# Power.net
KiCad netlist of a schematic drawn in Altium Designer
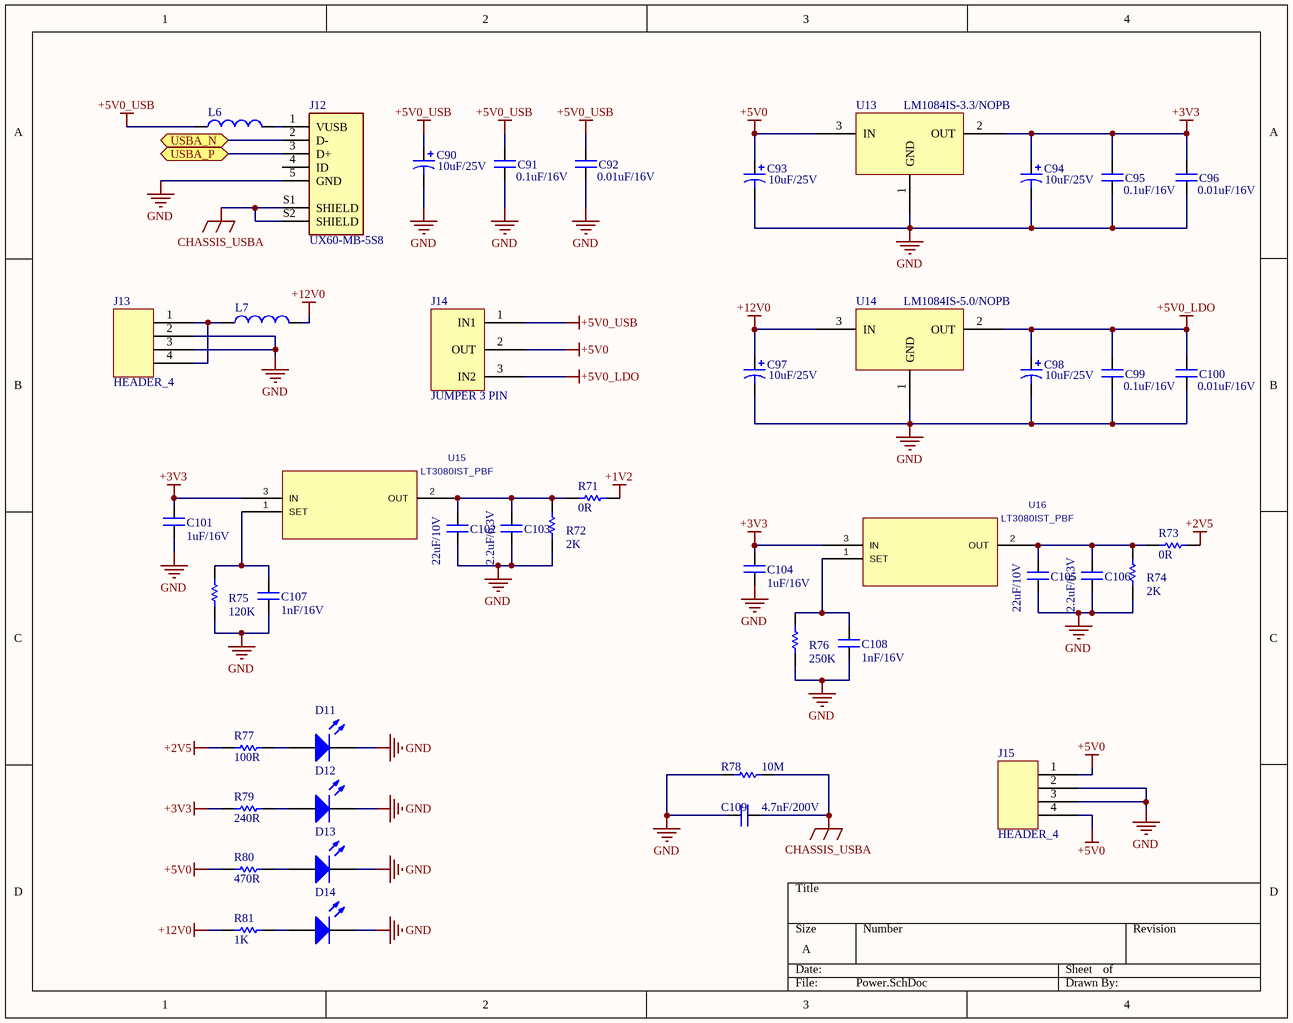
[diagram p0: Power.SchDoc]

(export (version "E")
  (design (tool "Eeschema 10.0.6"))
  (components
    (comp (ref "C90")
      (value "10uF/25V")
      (footprint "CASE-C")
      (fields (field (name "Comment") "CASE-C"))
      (libsource (lib "AdapterLib") (part "CASE-C"))
    )
    (comp (ref "C91")
      (value "0.1uF/16V")
      (footprint "CAP_0805")
      (fields (field (name "Comment") "CAP_0805"))
      (libsource (lib "AdapterLib") (part "CAP_0805"))
    )
    (comp (ref "C92")
      (value "0.01uF/16V")
      (footprint "CAP_0805")
      (fields (field (name "Comment") "CAP_0805"))
      (libsource (lib "AdapterLib") (part "CAP_0805"))
    )
    (comp (ref "C93")
      (value "10uF/25V")
      (footprint "CASE-C")
      (fields (field (name "Comment") "CASE-C"))
      (libsource (lib "AdapterLib") (part "CASE-C"))
    )
    (comp (ref "C94")
      (value "10uF/25V")
      (footprint "CASE-C")
      (fields (field (name "Comment") "CASE-C"))
      (libsource (lib "AdapterLib") (part "CASE-C"))
    )
    (comp (ref "C95")
      (value "0.1uF/16V")
      (footprint "CAP_0805")
      (fields (field (name "Comment") "CAP_0805"))
      (libsource (lib "AdapterLib") (part "CAP_0805"))
    )
    (comp (ref "C96")
      (value "0.01uF/16V")
      (footprint "CAP_0805")
      (fields (field (name "Comment") "CAP_0805"))
      (libsource (lib "AdapterLib") (part "CAP_0805"))
    )
    (comp (ref "C97")
      (value "10uF/25V")
      (footprint "CASE-C")
      (fields (field (name "Comment") "CASE-C"))
      (libsource (lib "AdapterLib") (part "CASE-C"))
    )
    (comp (ref "C98")
      (value "10uF/25V")
      (footprint "CASE-C")
      (fields (field (name "Comment") "CASE-C"))
      (libsource (lib "AdapterLib") (part "CASE-C"))
    )
    (comp (ref "C99")
      (value "0.1uF/16V")
      (footprint "CAP_0805")
      (fields (field (name "Comment") "CAP_0805"))
      (libsource (lib "AdapterLib") (part "CAP_0805"))
    )
    (comp (ref "C100")
      (value "0.01uF/16V")
      (footprint "CAP_0805")
      (fields (field (name "Comment") "CAP_0805"))
      (libsource (lib "AdapterLib") (part "CAP_0805"))
    )
    (comp (ref "C101")
      (value "1uF/16V")
      (footprint "CAP_0805")
      (fields (field (name "Comment") "CAP_0805"))
      (libsource (lib "AdapterLib") (part "CAP_0805"))
    )
    (comp (ref "C102")
      (value "22uF/10V")
      (footprint "CAP_0805")
      (fields (field (name "Comment") "CAP_0805"))
      (libsource (lib "AdapterLib") (part "CAP_0805"))
    )
    (comp (ref "C103")
      (value "2.2uF/6.3V")
      (footprint "CAP_0805")
      (fields (field (name "Comment") "CAP_0805"))
      (libsource (lib "AdapterLib") (part "CAP_0805"))
    )
    (comp (ref "C104")
      (value "1uF/16V")
      (footprint "CAP_0805")
      (fields (field (name "Comment") "CAP_0805"))
      (libsource (lib "AdapterLib") (part "CAP_0805"))
    )
    (comp (ref "C105")
      (value "22uF/10V")
      (footprint "CAP_0805")
      (fields (field (name "Comment") "CAP_0805"))
      (libsource (lib "AdapterLib") (part "CAP_0805"))
    )
    (comp (ref "C106")
      (value "2.2uF/6.3V")
      (footprint "CAP_0805")
      (fields (field (name "Comment") "CAP_0805"))
      (libsource (lib "AdapterLib") (part "CAP_0805"))
    )
    (comp (ref "C107")
      (value "1nF/16V")
      (footprint "CAP_0805")
      (fields (field (name "Comment") "CAP_0805"))
      (libsource (lib "AdapterLib") (part "CAP_0805"))
    )
    (comp (ref "C108")
      (value "1nF/16V")
      (footprint "CAP_0805")
      (fields (field (name "Comment") "CAP_0805"))
      (libsource (lib "AdapterLib") (part "CAP_0805"))
    )
    (comp (ref "C109")
      (value "4.7nF/200V")
      (footprint "CAP_0805")
      (fields (field (name "Comment") "CAP_0805"))
      (libsource (lib "AdapterLib") (part "CAP_0805"))
    )
    (comp (ref "D11")
      (value "LED_0603")
      (footprint "LED_0603")
      (libsource (lib "AdapterLib") (part "LED_0603"))
    )
    (comp (ref "D12")
      (value "LED_0603")
      (footprint "LED_0603")
      (libsource (lib "AdapterLib") (part "LED_0603"))
    )
    (comp (ref "D13")
      (value "LED_0603")
      (footprint "LED_0603")
      (libsource (lib "AdapterLib") (part "LED_0603"))
    )
    (comp (ref "D14")
      (value "LED_0603")
      (footprint "LED_0603")
      (libsource (lib "AdapterLib") (part "LED_0603"))
    )
    (comp (ref "J12")
      (value "UX60-MB-5S8")
      (footprint "UX60-MB-5S8")
      (description "USB MINI TYPE B")
      (libsource (lib "AdapterLib") (part "UX60-MB-5S8"))
    )
    (comp (ref "J13")
      (value "HEADER_4")
      (footprint "HEADER_4")
      (libsource (lib "AdapterLib") (part "HEADER_4"))
    )
    (comp (ref "J14")
      (value "JUMPER 3 PIN")
      (footprint "JUMPER 3 PIN")
      (libsource (lib "AdapterLib") (part "JUMPER 3 PIN"))
    )
    (comp (ref "J15")
      (value "HEADER_4")
      (footprint "HEADER_4")
      (libsource (lib "AdapterLib") (part "HEADER_4"))
    )
    (comp (ref "L6")
      (value "IND_0805")
      (footprint "IND_0805")
      (libsource (lib "AdapterLib") (part "IND_0805"))
    )
    (comp (ref "L7")
      (value "IND_0805")
      (footprint "IND_0805")
      (libsource (lib "AdapterLib") (part "IND_0805"))
    )
    (comp (ref "R71")
      (value "0R")
      (footprint "RES_0805")
      (fields (field (name "Comment") "RES_0805"))
      (libsource (lib "AdapterLib") (part "RES_0805"))
    )
    (comp (ref "R72")
      (value "2K")
      (footprint "RES_0805")
      (fields (field (name "Comment") "RES_0805"))
      (libsource (lib "AdapterLib") (part "RES_0805"))
    )
    (comp (ref "R73")
      (value "0R")
      (footprint "RES_0805")
      (fields (field (name "Comment") "RES_0805"))
      (libsource (lib "AdapterLib") (part "RES_0805"))
    )
    (comp (ref "R74")
      (value "2K")
      (footprint "RES_0805")
      (fields (field (name "Comment") "RES_0805"))
      (libsource (lib "AdapterLib") (part "RES_0805"))
    )
    (comp (ref "R75")
      (value "120K")
      (footprint "RES_0805")
      (fields (field (name "Comment") "RES_0805"))
      (libsource (lib "AdapterLib") (part "RES_0805"))
    )
    (comp (ref "R76")
      (value "250K")
      (footprint "RES_0805")
      (fields (field (name "Comment") "RES_0805"))
      (libsource (lib "AdapterLib") (part "RES_0805"))
    )
    (comp (ref "R77")
      (value "100R")
      (footprint "RES_0805")
      (fields (field (name "Comment") "RES_0805"))
      (libsource (lib "AdapterLib") (part "RES_0805"))
    )
    (comp (ref "R78")
      (value "10M")
      (footprint "RES_0805")
      (fields (field (name "Comment") "RES_0805"))
      (libsource (lib "AdapterLib") (part "RES_0805"))
    )
    (comp (ref "R79")
      (value "240R")
      (footprint "RES_0805")
      (fields (field (name "Comment") "RES_0805"))
      (libsource (lib "AdapterLib") (part "RES_0805"))
    )
    (comp (ref "R80")
      (value "470R")
      (footprint "RES_0805")
      (fields (field (name "Comment") "RES_0805"))
      (libsource (lib "AdapterLib") (part "RES_0805"))
    )
    (comp (ref "R81")
      (value "1K")
      (footprint "RES_0805")
      (fields (field (name "Comment") "RES_0805"))
      (libsource (lib "AdapterLib") (part "RES_0805"))
    )
    (comp (ref "U13")
      (value "LM1084IS-3.3/NOPB")
      (footprint "LM1084IS-3.3/NOPB")
      (libsource (lib "AdapterLib") (part "LM1084IS-3.3/NOPB"))
    )
    (comp (ref "U14")
      (value "LM1084IS-5.0/NOPB")
      (footprint "LM1084IS-5.0/NOPB")
      (libsource (lib "AdapterLib") (part "LM1084IS-5.0/NOPB"))
    )
    (comp (ref "U15")
      (value "LT3080IST_PBF")
      (footprint "LT3080IST_PBF")
      (fields (field (name "MANUFACTURER_PART_NUMBER") "LT3080IST#PBF"))
      (libsource (lib "AdapterLib") (part "LT3080IST_PBF"))
    )
    (comp (ref "U16")
      (value "LT3080IST_PBF")
      (footprint "LT3080IST_PBF")
      (fields (field (name "MANUFACTURER_PART_NUMBER") "LT3080IST#PBF"))
      (libsource (lib "AdapterLib") (part "LT3080IST_PBF"))
    )
  )
  (nets
    (net (code "1") (name "+1V2") (class "Default")
      (node (ref "R71") (pin "1") (pinfunction "1_1") (pintype "passive"))
    )
    (net (code "2") (name "+2V5") (class "Default")
      (node (ref "R73") (pin "1") (pinfunction "1_1") (pintype "passive"))
      (node (ref "R77") (pin "1") (pinfunction "1_1") (pintype "passive"))
    )
    (net (code "3") (name "+3V3") (class "Default")
      (node (ref "C101") (pin "2") (pinfunction "2_2") (pintype "passive"))
      (node (ref "C104") (pin "2") (pinfunction "2_2") (pintype "passive"))
      (node (ref "C94") (pin "A") (pinfunction "1_A") (pintype "passive"))
      (node (ref "C95") (pin "2") (pinfunction "2_2") (pintype "passive"))
      (node (ref "C96") (pin "2") (pinfunction "2_2") (pintype "passive"))
      (node (ref "R79") (pin "1") (pinfunction "1_1") (pintype "passive"))
      (node (ref "U13") (pin "2") (pinfunction "OUT_2") (pintype "passive"))
      (node (ref "U15") (pin "3") (pinfunction "IN_3") (pintype "passive"))
      (node (ref "U16") (pin "3") (pinfunction "IN_3") (pintype "passive"))
    )
    (net (code "4") (name "+5V0") (class "Default")
      (node (ref "C93") (pin "A") (pinfunction "1_A") (pintype "passive"))
      (node (ref "J14") (pin "2") (pinfunction "OUT_2") (pintype "passive"))
      (node (ref "J15") (pin "1") (pintype "passive"))
      (node (ref "J15") (pin "4") (pintype "passive"))
      (node (ref "R80") (pin "1") (pinfunction "1_1") (pintype "passive"))
      (node (ref "U13") (pin "3") (pinfunction "IN_3") (pintype "passive"))
    )
    (net (code "5") (name "+5V0_LDO") (class "Default")
      (node (ref "C100") (pin "2") (pinfunction "2_2") (pintype "passive"))
      (node (ref "C98") (pin "A") (pinfunction "1_A") (pintype "passive"))
      (node (ref "C99") (pin "2") (pinfunction "2_2") (pintype "passive"))
      (node (ref "J14") (pin "3") (pinfunction "IN2_3") (pintype "passive"))
      (node (ref "U14") (pin "2") (pinfunction "OUT_2") (pintype "passive"))
    )
    (net (code "6") (name "+5V0_USB") (class "Default")
      (node (ref "C90") (pin "A") (pinfunction "1_A") (pintype "passive"))
      (node (ref "C91") (pin "2") (pinfunction "2_2") (pintype "passive"))
      (node (ref "C92") (pin "2") (pinfunction "2_2") (pintype "passive"))
      (node (ref "J14") (pin "1") (pinfunction "IN1_1") (pintype "passive"))
      (node (ref "L6") (pin "1") (pinfunction "1_1") (pintype "passive"))
    )
    (net (code "7") (name "+12V0") (class "Default")
      (node (ref "C97") (pin "A") (pinfunction "1_A") (pintype "passive"))
      (node (ref "L7") (pin "2") (pinfunction "2_2") (pintype "passive"))
      (node (ref "R81") (pin "1") (pinfunction "1_1") (pintype "passive"))
      (node (ref "U14") (pin "3") (pinfunction "IN_3") (pintype "passive"))
    )
    (net (code "8") (name "/USBA_N") (class "Default")
      (node (ref "J12") (pin "2") (pinfunction "D-_2") (pintype "passive"))
    )
    (net (code "9") (name "/USBA_P") (class "Default")
      (node (ref "J12") (pin "3") (pinfunction "D+_3") (pintype "passive"))
    )
    (net (code "10") (name "CHASSIS_USBA") (class "Default")
      (node (ref "C109") (pin "1") (pinfunction "1_1") (pintype "passive"))
      (node (ref "J12") (pin "S1") (pinfunction "SHIELD_S1") (pintype "passive"))
      (node (ref "J12") (pin "S2") (pinfunction "SHIELD_S2") (pintype "passive"))
      (node (ref "R78") (pin "1") (pinfunction "1_1") (pintype "passive"))
    )
    (net (code "11") (name "GND") (class "Default")
      (node (ref "C100") (pin "1") (pinfunction "1_1") (pintype "passive"))
      (node (ref "C101") (pin "1") (pinfunction "1_1") (pintype "passive"))
      (node (ref "C102") (pin "1") (pinfunction "1_1") (pintype "passive"))
      (node (ref "C103") (pin "1") (pinfunction "1_1") (pintype "passive"))
      (node (ref "C104") (pin "1") (pinfunction "1_1") (pintype "passive"))
      (node (ref "C105") (pin "1") (pinfunction "1_1") (pintype "passive"))
      (node (ref "C106") (pin "1") (pinfunction "1_1") (pintype "passive"))
      (node (ref "C107") (pin "1") (pinfunction "1_1") (pintype "passive"))
      (node (ref "C108") (pin "1") (pinfunction "1_1") (pintype "passive"))
      (node (ref "C109") (pin "2") (pinfunction "2_2") (pintype "passive"))
      (node (ref "C90") (pin "K") (pinfunction "2_K") (pintype "passive"))
      (node (ref "C91") (pin "1") (pinfunction "1_1") (pintype "passive"))
      (node (ref "C92") (pin "1") (pinfunction "1_1") (pintype "passive"))
      (node (ref "C93") (pin "K") (pinfunction "2_K") (pintype "passive"))
      (node (ref "C94") (pin "K") (pinfunction "2_K") (pintype "passive"))
      (node (ref "C95") (pin "1") (pinfunction "1_1") (pintype "passive"))
      (node (ref "C96") (pin "1") (pinfunction "1_1") (pintype "passive"))
      (node (ref "C97") (pin "K") (pinfunction "2_K") (pintype "passive"))
      (node (ref "C98") (pin "K") (pinfunction "2_K") (pintype "passive"))
      (node (ref "C99") (pin "1") (pinfunction "1_1") (pintype "passive"))
      (node (ref "D11") (pin "2") (pinfunction "K_2") (pintype "passive"))
      (node (ref "D12") (pin "2") (pinfunction "K_2") (pintype "passive"))
      (node (ref "D13") (pin "2") (pinfunction "K_2") (pintype "passive"))
      (node (ref "D14") (pin "2") (pinfunction "K_2") (pintype "passive"))
      (node (ref "J12") (pin "5") (pinfunction "GND_5") (pintype "passive"))
      (node (ref "J13") (pin "2") (pintype "passive"))
      (node (ref "J13") (pin "3") (pintype "passive"))
      (node (ref "J15") (pin "2") (pintype "passive"))
      (node (ref "J15") (pin "3") (pintype "passive"))
      (node (ref "R72") (pin "1") (pinfunction "1_1") (pintype "passive"))
      (node (ref "R74") (pin "1") (pinfunction "1_1") (pintype "passive"))
      (node (ref "R75") (pin "1") (pinfunction "1_1") (pintype "passive"))
      (node (ref "R76") (pin "1") (pinfunction "1_1") (pintype "passive"))
      (node (ref "R78") (pin "2") (pinfunction "2_2") (pintype "passive"))
      (node (ref "U13") (pin "1") (pinfunction "GND_1") (pintype "passive"))
      (node (ref "U14") (pin "1") (pinfunction "GND_1") (pintype "passive"))
    )
    (net (code "12") (name "Net-(D11-A)") (class "Default")
      (node (ref "D11") (pin "1") (pinfunction "A_1") (pintype "passive"))
      (node (ref "R77") (pin "2") (pinfunction "2_2") (pintype "passive"))
    )
    (net (code "13") (name "Net-(D12-A)") (class "Default")
      (node (ref "D12") (pin "1") (pinfunction "A_1") (pintype "passive"))
      (node (ref "R79") (pin "2") (pinfunction "2_2") (pintype "passive"))
    )
    (net (code "14") (name "Net-(D13-A)") (class "Default")
      (node (ref "D13") (pin "1") (pinfunction "A_1") (pintype "passive"))
      (node (ref "R80") (pin "2") (pinfunction "2_2") (pintype "passive"))
    )
    (net (code "15") (name "Net-(D14-A)") (class "Default")
      (node (ref "D14") (pin "1") (pinfunction "A_1") (pintype "passive"))
      (node (ref "R81") (pin "2") (pinfunction "2_2") (pintype "passive"))
    )
    (net (code "16") (name "Net-(J12-VUSB)") (class "Default")
      (node (ref "J12") (pin "1") (pinfunction "VUSB_1") (pintype "passive"))
      (node (ref "L6") (pin "2") (pinfunction "2_2") (pintype "passive"))
    )
    (net (code "17") (name "Net-(J13-Pad1)") (class "Default")
      (node (ref "J13") (pin "1") (pintype "passive"))
      (node (ref "J13") (pin "4") (pintype "passive"))
      (node (ref "L7") (pin "1") (pinfunction "1_1") (pintype "passive"))
    )
    (net (code "18") (name "Net-(U15-OUT)") (class "Default")
      (node (ref "C102") (pin "2") (pinfunction "2_2") (pintype "passive"))
      (node (ref "C103") (pin "2") (pinfunction "2_2") (pintype "passive"))
      (node (ref "R71") (pin "2") (pinfunction "2_2") (pintype "passive"))
      (node (ref "R72") (pin "2") (pinfunction "2_2") (pintype "passive"))
      (node (ref "U15") (pin "2") (pinfunction "OUT_2") (pintype "passive"))
    )
    (net (code "19") (name "Net-(U15-SET)") (class "Default")
      (node (ref "C107") (pin "2") (pinfunction "2_2") (pintype "passive"))
      (node (ref "R75") (pin "2") (pinfunction "2_2") (pintype "passive"))
      (node (ref "U15") (pin "1") (pinfunction "SET_1") (pintype "passive"))
    )
    (net (code "20") (name "Net-(U16-OUT)") (class "Default")
      (node (ref "C105") (pin "2") (pinfunction "2_2") (pintype "passive"))
      (node (ref "C106") (pin "2") (pinfunction "2_2") (pintype "passive"))
      (node (ref "R73") (pin "2") (pinfunction "2_2") (pintype "passive"))
      (node (ref "R74") (pin "2") (pinfunction "2_2") (pintype "passive"))
      (node (ref "U16") (pin "2") (pinfunction "OUT_2") (pintype "passive"))
    )
    (net (code "21") (name "Net-(U16-SET)") (class "Default")
      (node (ref "C108") (pin "2") (pinfunction "2_2") (pintype "passive"))
      (node (ref "R76") (pin "2") (pinfunction "2_2") (pintype "passive"))
      (node (ref "U16") (pin "1") (pinfunction "SET_1") (pintype "passive"))
    )
    (net (code "22") (name "unconnected-(J12-ID-Pad4)") (class "Default")
      (node (ref "J12") (pin "4") (pinfunction "ID_4") (pintype "passive"))
    )
  )
)
